# Adafruit_Feather_ESP32-C6-AUSSEN.net
KiCad netlist of a schematic drawn in EAGLE
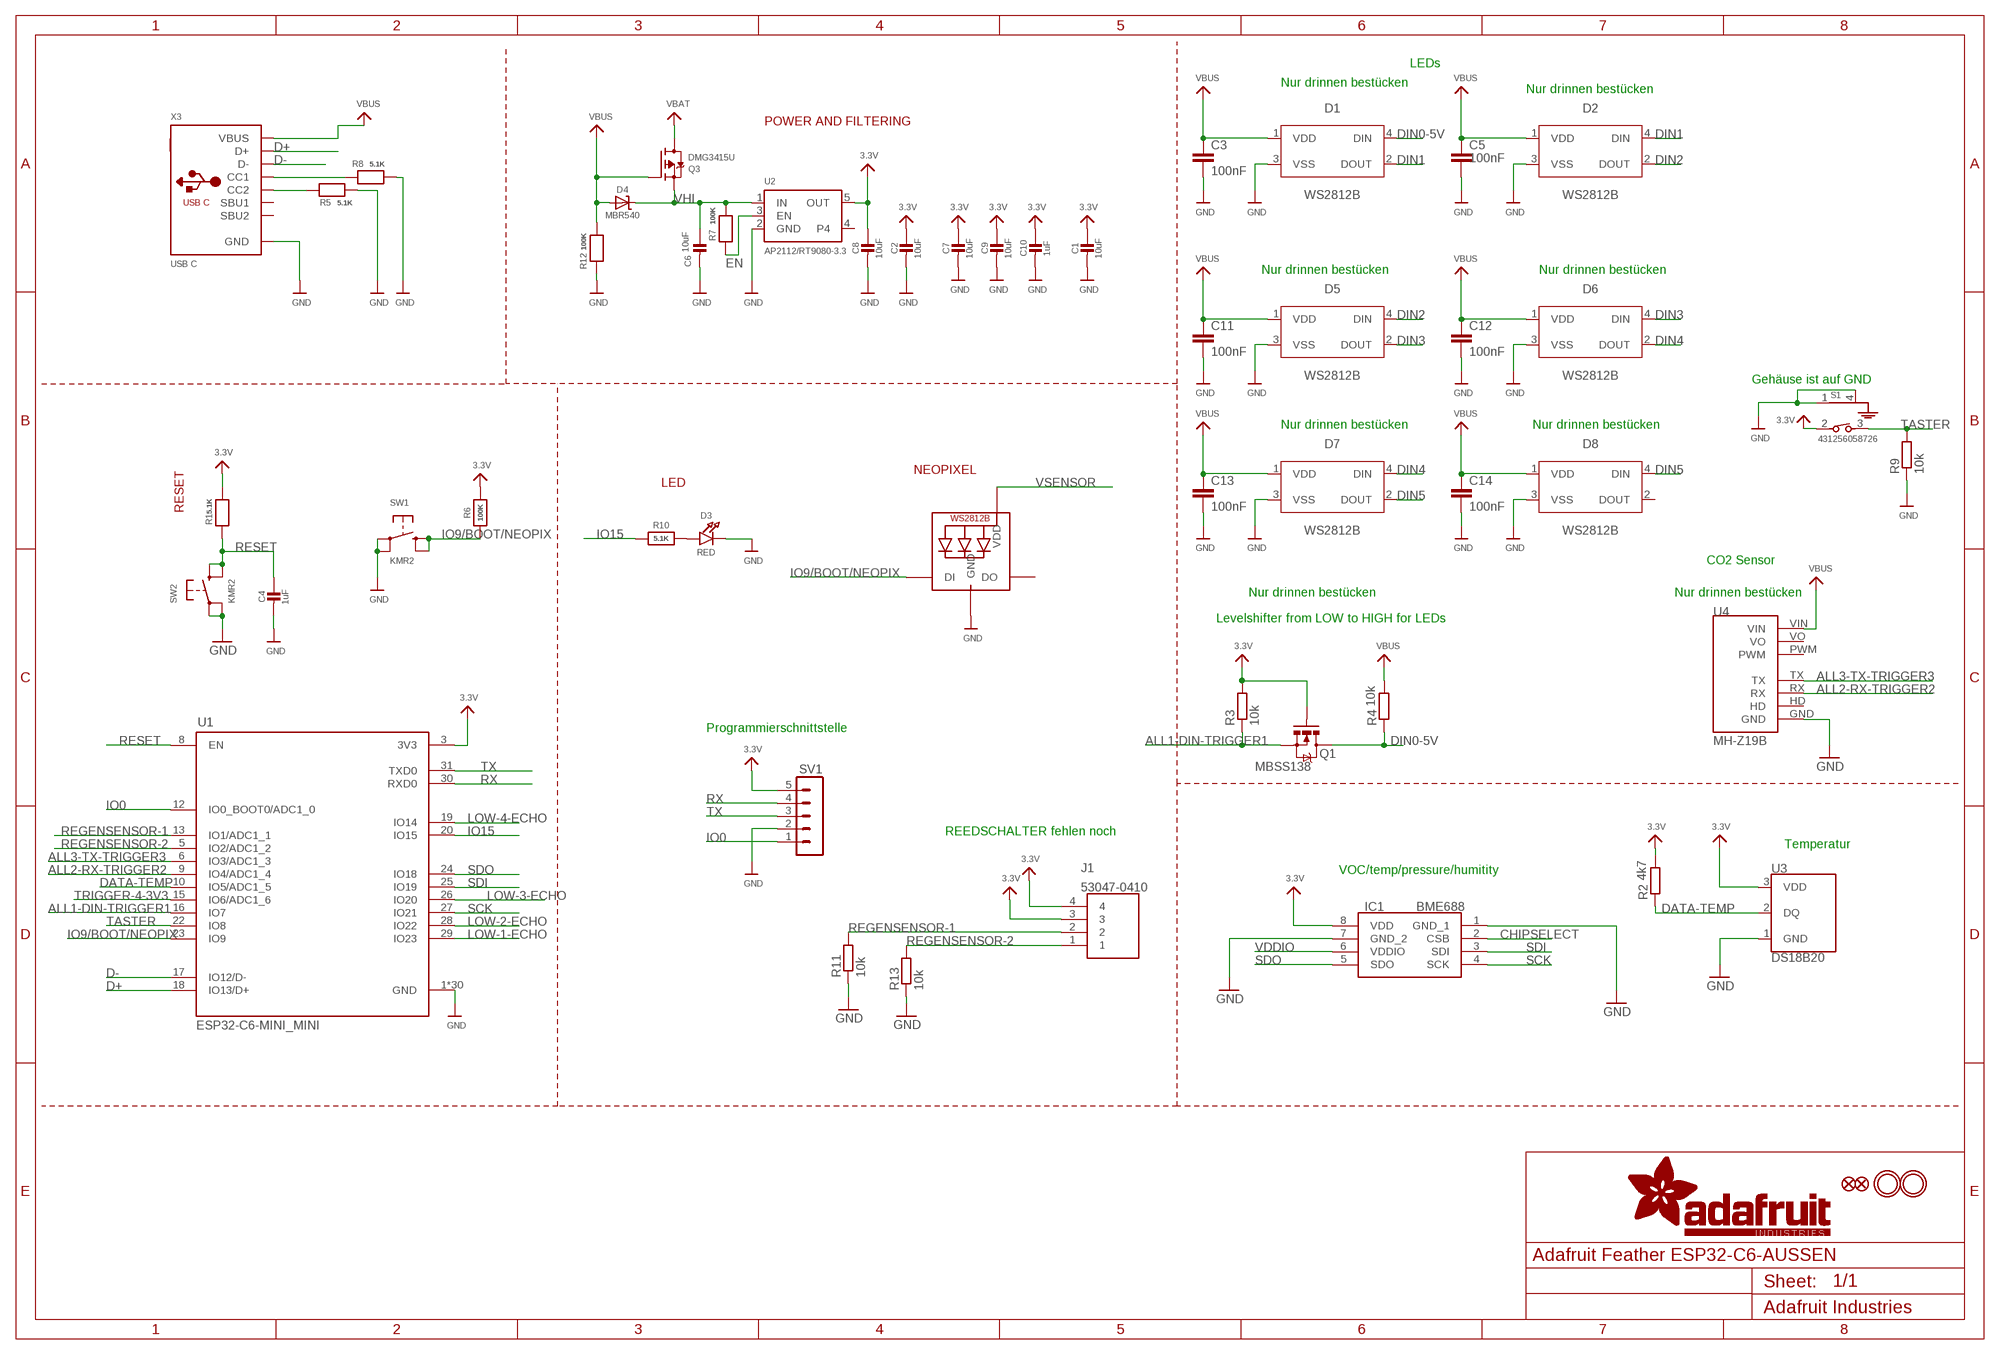
[diagram p0: schematic, sheet 1, part 1 of 2]
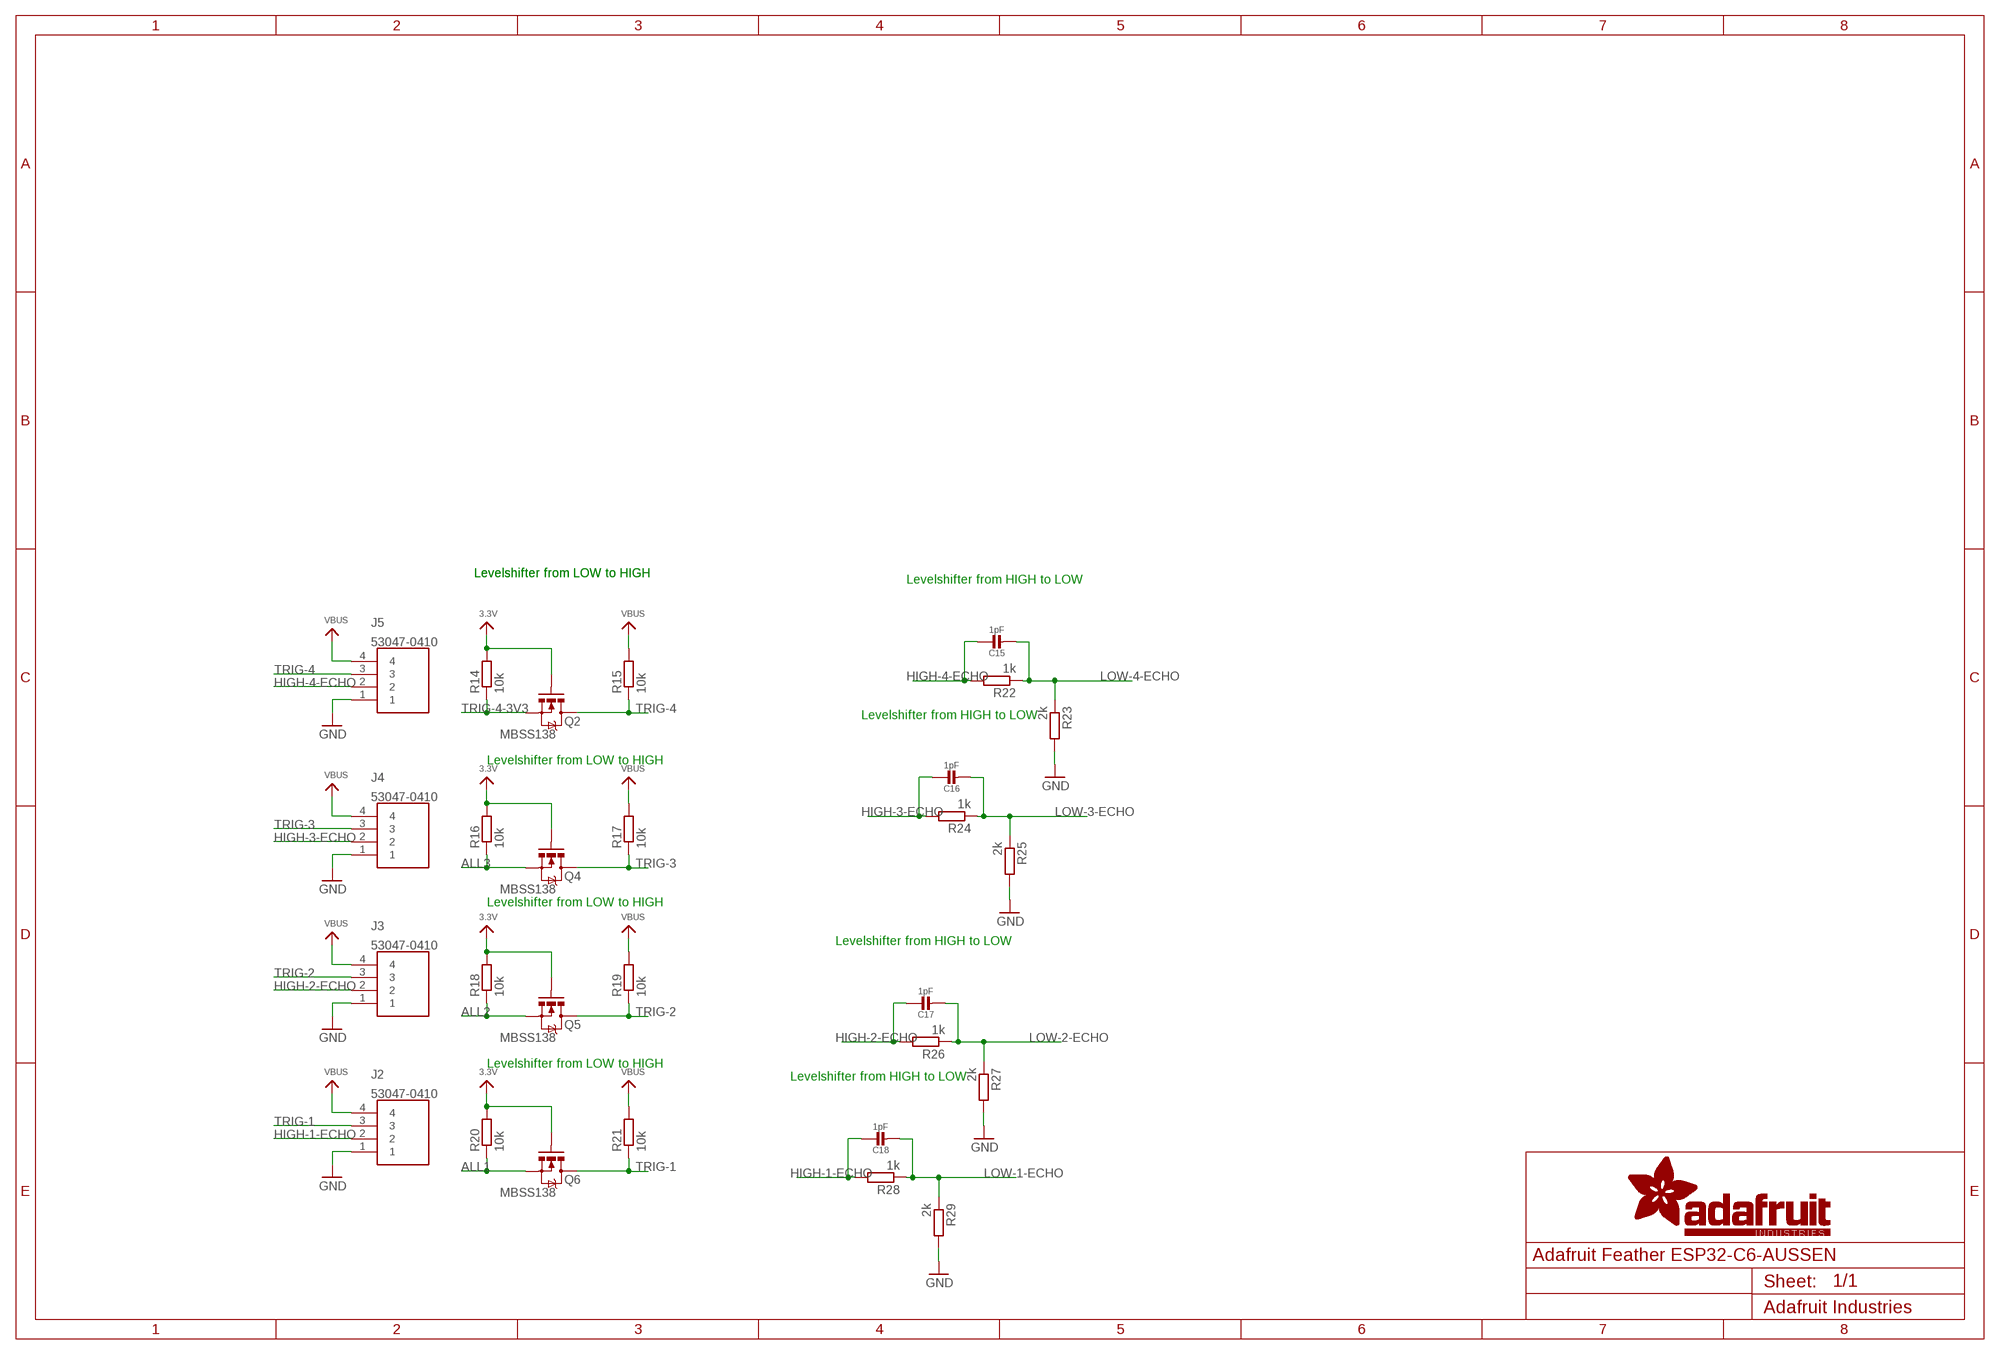
[diagram p1: schematic, sheet 1, part 2 of 2]

(export (version "E")
  (design (tool "Eeschema 10.0.6"))
  (components
    (comp (ref "C1")
      (value "10uF")
      (footprint "eagle-import:0805-NO")
      (libsource (lib "eagle-import") (part "CAP_CERAMIC0805-NOOUTLINE"))
    )
    (comp (ref "C2")
      (value "10uF")
      (footprint "eagle-import:0805-NO")
      (libsource (lib "eagle-import") (part "CAP_CERAMIC0805-NOOUTLINE"))
    )
    (comp (ref "C3")
      (value "100nF")
      (footprint "eagle-import:C0603")
      (libsource (lib "eagle-import") (part "C-EUC0603"))
    )
    (comp (ref "C4")
      (value "1uF")
      (footprint "eagle-import:0603-NO")
      (libsource (lib "eagle-import") (part "CAP_CERAMIC0603_NO"))
    )
    (comp (ref "C5")
      (value "100nF")
      (footprint "eagle-import:C0603")
      (libsource (lib "eagle-import") (part "C-EUC0603"))
    )
    (comp (ref "C6")
      (value "10uF")
      (footprint "eagle-import:0805-NO")
      (libsource (lib "eagle-import") (part "CAP_CERAMIC0805-NOOUTLINE"))
    )
    (comp (ref "C7")
      (value "10uF")
      (footprint "eagle-import:0805-NO")
      (libsource (lib "eagle-import") (part "CAP_CERAMIC0805-NOOUTLINE"))
    )
    (comp (ref "C8")
      (value "10uF")
      (footprint "eagle-import:0805-NO")
      (fields (field (name "REV") "B"))
      (libsource (lib "eagle-import") (part "CAP_CERAMIC0805-NOOUTLINE"))
    )
    (comp (ref "C9")
      (value "10uF")
      (footprint "eagle-import:0805-NO")
      (libsource (lib "eagle-import") (part "CAP_CERAMIC0805-NOOUTLINE"))
    )
    (comp (ref "C10")
      (value "1uF")
      (footprint "eagle-import:0603-NO")
      (libsource (lib "eagle-import") (part "CAP_CERAMIC0603_NO"))
    )
    (comp (ref "C11")
      (value "100nF")
      (footprint "eagle-import:C0603")
      (libsource (lib "eagle-import") (part "C-EUC0603"))
    )
    (comp (ref "C12")
      (value "100nF")
      (footprint "eagle-import:C0603")
      (libsource (lib "eagle-import") (part "C-EUC0603"))
    )
    (comp (ref "C13")
      (value "100nF")
      (footprint "eagle-import:C0603")
      (libsource (lib "eagle-import") (part "C-EUC0603"))
    )
    (comp (ref "C14")
      (value "100nF")
      (footprint "eagle-import:C0603")
      (libsource (lib "eagle-import") (part "C-EUC0603"))
    )
    (comp (ref "C15")
      (value "1pF")
      (footprint "eagle-import:0603-NO")
      (libsource (lib "eagle-import") (part "CAP_CERAMIC0603_NO"))
    )
    (comp (ref "C16")
      (value "1pF")
      (footprint "eagle-import:0603-NO")
      (libsource (lib "eagle-import") (part "CAP_CERAMIC0603_NO"))
    )
    (comp (ref "C17")
      (value "1pF")
      (footprint "eagle-import:0603-NO")
      (libsource (lib "eagle-import") (part "CAP_CERAMIC0603_NO"))
    )
    (comp (ref "C18")
      (value "1pF")
      (footprint "eagle-import:0603-NO")
      (libsource (lib "eagle-import") (part "CAP_CERAMIC0603_NO"))
    )
    (comp (ref "D1")
      (value "WS2812B")
      (footprint "eagle-import:WS2812B")
      (fields (field (name "MANUFACTURER") "Worldsemi"))
      (libsource (lib "eagle-import") (part "WS2812B"))
    )
    (comp (ref "D2")
      (value "WS2812B")
      (footprint "eagle-import:WS2812B")
      (fields (field (name "MANUFACTURER") "Worldsemi"))
      (libsource (lib "eagle-import") (part "WS2812B"))
    )
    (comp (ref "D3")
      (value "RED")
      (footprint "eagle-import:CHIPLED_0603_NOOUTLINE")
      (libsource (lib "eagle-import") (part "LED0603_NOOUTLINE"))
    )
    (comp (ref "D4")
      (value "MBR540")
      (footprint "eagle-import:SOD-123")
      (libsource (lib "eagle-import") (part "DIODE-SCHOTTKYSOD-123"))
    )
    (comp (ref "D5")
      (value "WS2812B")
      (footprint "eagle-import:WS2812B")
      (fields (field (name "MANUFACTURER") "Worldsemi"))
      (libsource (lib "eagle-import") (part "WS2812B"))
    )
    (comp (ref "D6")
      (value "WS2812B")
      (footprint "eagle-import:WS2812B")
      (fields (field (name "MANUFACTURER") "Worldsemi"))
      (libsource (lib "eagle-import") (part "WS2812B"))
    )
    (comp (ref "D7")
      (value "WS2812B")
      (footprint "eagle-import:WS2812B")
      (fields (field (name "MANUFACTURER") "Worldsemi"))
      (libsource (lib "eagle-import") (part "WS2812B"))
    )
    (comp (ref "D8")
      (value "WS2812B")
      (footprint "eagle-import:WS2812B")
      (fields (field (name "MANUFACTURER") "Worldsemi"))
      (libsource (lib "eagle-import") (part "WS2812B"))
    )
    (comp (ref "IC1")
      (value "BME688")
      (footprint "eagle-import:BME688")
      (fields (field (name "MOUSER_PART_NUMBER") "262-BME688"))
      (libsource (lib "eagle-import") (part "BME688"))
    )
    (comp (ref "J1")
      (value "53047-0410")
      (footprint "eagle-import:530470410")
      (fields (field (name "MOUSER_PART_NUMBER") "538-53047-0410"))
      (libsource (lib "eagle-import") (part "53047-0410"))
    )
    (comp (ref "J2")
      (value "53047-0410")
      (footprint "eagle-import:530470410")
      (fields (field (name "MOUSER_PART_NUMBER") "538-53047-0410"))
      (libsource (lib "eagle-import") (part "53047-0410"))
    )
    (comp (ref "J3")
      (value "53047-0410")
      (footprint "eagle-import:530470410")
      (fields (field (name "MOUSER_PART_NUMBER") "538-53047-0410"))
      (libsource (lib "eagle-import") (part "53047-0410"))
    )
    (comp (ref "J4")
      (value "53047-0410")
      (footprint "eagle-import:530470410")
      (fields (field (name "MOUSER_PART_NUMBER") "538-53047-0410"))
      (libsource (lib "eagle-import") (part "53047-0410"))
    )
    (comp (ref "J5")
      (value "53047-0410")
      (footprint "eagle-import:530470410")
      (fields (field (name "MOUSER_PART_NUMBER") "538-53047-0410"))
      (libsource (lib "eagle-import") (part "53047-0410"))
    )
    (comp (ref "LED1")
      (value "WS2812B_3535FULL")
      (footprint "eagle-import:LED3535_FULLPADS")
      (libsource (lib "eagle-import") (part "WS2812B_3535FULL"))
    )
    (comp (ref "Q1")
      (value "MBSS138")
      (footprint "eagle-import:SOT23")
      (libsource (lib "eagle-import") (part "MOSFET-NCHANNELBSS138"))
    )
    (comp (ref "Q2")
      (value "MBSS138")
      (footprint "eagle-import:SOT23")
      (libsource (lib "eagle-import") (part "MOSFET-NCHANNELBSS138"))
    )
    (comp (ref "Q3")
      (value "DMG3415U")
      (footprint "eagle-import:SOT23-R")
      (libsource (lib "eagle-import") (part "MOSFET-P"))
    )
    (comp (ref "Q4")
      (value "MBSS138")
      (footprint "eagle-import:SOT23")
      (libsource (lib "eagle-import") (part "MOSFET-NCHANNELBSS138"))
    )
    (comp (ref "Q5")
      (value "MBSS138")
      (footprint "eagle-import:SOT23")
      (libsource (lib "eagle-import") (part "MOSFET-NCHANNELBSS138"))
    )
    (comp (ref "Q6")
      (value "MBSS138")
      (footprint "eagle-import:SOT23")
      (libsource (lib "eagle-import") (part "MOSFET-NCHANNELBSS138"))
    )
    (comp (ref "R1")
      (value "5.1K")
      (footprint "eagle-import:0603-NO")
      (libsource (lib "eagle-import") (part "RESISTOR_0603_NOOUT"))
    )
    (comp (ref "R2")
      (value "4k7")
      (footprint "eagle-import:0207_12")
      (libsource (lib "eagle-import") (part "R-EU_0207/12"))
    )
    (comp (ref "R3")
      (value "10k")
      (footprint "eagle-import:0207_12")
      (libsource (lib "eagle-import") (part "R-EU_0207/12"))
    )
    (comp (ref "R4")
      (value "10k")
      (footprint "eagle-import:0207_12")
      (libsource (lib "eagle-import") (part "R-EU_0207/12"))
    )
    (comp (ref "R5")
      (value "5.1K")
      (footprint "eagle-import:0603-NO")
      (libsource (lib "eagle-import") (part "RESISTOR_0603_NOOUT"))
    )
    (comp (ref "R6")
      (value "100K")
      (footprint "eagle-import:0603-NO")
      (libsource (lib "eagle-import") (part "RESISTOR_0603_NOOUT"))
    )
    (comp (ref "R7")
      (value "100K")
      (footprint "eagle-import:0603-NO")
      (libsource (lib "eagle-import") (part "RESISTOR_0603_NOOUT"))
    )
    (comp (ref "R8")
      (value "5.1K")
      (footprint "eagle-import:0603-NO")
      (libsource (lib "eagle-import") (part "RESISTOR_0603_NOOUT"))
    )
    (comp (ref "R9")
      (value "10k")
      (footprint "eagle-import:0207_12")
      (libsource (lib "eagle-import") (part "R-EU_0207/12"))
    )
    (comp (ref "R10")
      (value "5.1K")
      (footprint "eagle-import:0603-NO")
      (libsource (lib "eagle-import") (part "RESISTOR_0603_NOOUT"))
    )
    (comp (ref "R11")
      (value "10k")
      (footprint "eagle-import:0207_12")
      (libsource (lib "eagle-import") (part "R-EU_0207/12"))
    )
    (comp (ref "R12")
      (value "100K")
      (footprint "eagle-import:0603-NO")
      (libsource (lib "eagle-import") (part "RESISTOR_0603_NOOUT"))
    )
    (comp (ref "R13")
      (value "10k")
      (footprint "eagle-import:0207_12")
      (libsource (lib "eagle-import") (part "R-EU_0207/12"))
    )
    (comp (ref "R14")
      (value "10k")
      (footprint "eagle-import:0207_12")
      (libsource (lib "eagle-import") (part "R-EU_0207/12"))
    )
    (comp (ref "R15")
      (value "10k")
      (footprint "eagle-import:0207_12")
      (libsource (lib "eagle-import") (part "R-EU_0207/12"))
    )
    (comp (ref "R16")
      (value "10k")
      (footprint "eagle-import:0207_12")
      (libsource (lib "eagle-import") (part "R-EU_0207/12"))
    )
    (comp (ref "R17")
      (value "10k")
      (footprint "eagle-import:0207_12")
      (libsource (lib "eagle-import") (part "R-EU_0207/12"))
    )
    (comp (ref "R18")
      (value "10k")
      (footprint "eagle-import:0207_12")
      (libsource (lib "eagle-import") (part "R-EU_0207/12"))
    )
    (comp (ref "R19")
      (value "10k")
      (footprint "eagle-import:0207_12")
      (libsource (lib "eagle-import") (part "R-EU_0207/12"))
    )
    (comp (ref "R20")
      (value "10k")
      (footprint "eagle-import:0207_12")
      (libsource (lib "eagle-import") (part "R-EU_0207/12"))
    )
    (comp (ref "R21")
      (value "10k")
      (footprint "eagle-import:0207_12")
      (libsource (lib "eagle-import") (part "R-EU_0207/12"))
    )
    (comp (ref "R22")
      (value "1k")
      (footprint "eagle-import:0207_12")
      (libsource (lib "eagle-import") (part "R-EU_0207/12"))
    )
    (comp (ref "R23")
      (value "2k")
      (footprint "eagle-import:0207_12")
      (libsource (lib "eagle-import") (part "R-EU_0207/12"))
    )
    (comp (ref "R24")
      (value "1k")
      (footprint "eagle-import:0207_12")
      (libsource (lib "eagle-import") (part "R-EU_0207/12"))
    )
    (comp (ref "R25")
      (value "2k")
      (footprint "eagle-import:0207_12")
      (libsource (lib "eagle-import") (part "R-EU_0207/12"))
    )
    (comp (ref "R26")
      (value "1k")
      (footprint "eagle-import:0207_12")
      (libsource (lib "eagle-import") (part "R-EU_0207/12"))
    )
    (comp (ref "R27")
      (value "2k")
      (footprint "eagle-import:0207_12")
      (libsource (lib "eagle-import") (part "R-EU_0207/12"))
    )
    (comp (ref "R28")
      (value "1k")
      (footprint "eagle-import:0207_12")
      (libsource (lib "eagle-import") (part "R-EU_0207/12"))
    )
    (comp (ref "R29")
      (value "2k")
      (footprint "eagle-import:0207_12")
      (libsource (lib "eagle-import") (part "R-EU_0207/12"))
    )
    (comp (ref "S1")
      (value "431256058726")
      (footprint "eagle-import:4312560587X6")
      (fields (field (name "MF") "Würth Elektronik") (field (name "MP") "431256058716"))
      (libsource (lib "eagle-import") (part "431256058726"))
    )
    (comp (ref "SV1")
      (value "MAR05-1")
      (footprint "eagle-import:MAR05-1")
      (libsource (lib "eagle-import") (part "MAR05-1"))
    )
    (comp (ref "SW1")
      (value "KMR2")
      (footprint "eagle-import:BTN_RKB2_4.6X2.8")
      (libsource (lib "eagle-import") (part "SWITCH_TACT_SMT_RKB2"))
    )
    (comp (ref "SW2")
      (value "KMR2")
      (footprint "eagle-import:BTN_RKB2_4.6X2.8")
      (libsource (lib "eagle-import") (part "SWITCH_TACT_SMT_RKB2"))
    )
    (comp (ref "U$31")
      (value "MOUNTINGHOLE2.5")
      (footprint "eagle-import:MOUNTINGHOLE_2.5_PLATED")
      (libsource (lib "eagle-import") (part "MOUNTINGHOLE2.5"))
    )
    (comp (ref "U$32")
      (value "MOUNTINGHOLE2.5")
      (footprint "eagle-import:MOUNTINGHOLE_2.5_PLATED")
      (libsource (lib "eagle-import") (part "MOUNTINGHOLE2.5"))
    )
    (comp (ref "U$34")
      (value "FIDUCIAL_1MM")
      (footprint "eagle-import:FIDUCIAL_1MM")
      (libsource (lib "eagle-import") (part "FIDUCIAL_1MM"))
    )
    (comp (ref "U$35")
      (value "FIDUCIAL_1MM")
      (footprint "eagle-import:FIDUCIAL_1MM")
      (libsource (lib "eagle-import") (part "FIDUCIAL_1MM"))
    )
    (comp (ref "U1")
      (value "ESP32-C6-MINI_MINI")
      (footprint "eagle-import:ESP32-PICO-MINI")
      (libsource (lib "eagle-import") (part "ESP32-C6-MINI_MINI"))
    )
    (comp (ref "U2")
      (value "AP2112/RT9080-3.3")
      (footprint "eagle-import:SOT23-5")
      (fields (field (name "JLC_ROTATION") "0"))
      (libsource (lib "eagle-import") (part "VREG_SOT23-5"))
    )
    (comp (ref "U3")
      (value "DS18B20")
      (footprint "eagle-import:TO-92-AMMO")
      (libsource (lib "eagle-import") (part "DS18B20"))
    )
    (comp (ref "U4")
      (value "MH-Z19B")
      (footprint "eagle-import:MH-Z19B")
      (fields (field (name "MF") "Winsen"))
      (libsource (lib "eagle-import") (part "MH-Z19B"))
    )
    (comp (ref "X3")
      (value "USB C")
      (footprint "eagle-import:USB_C_CUSB31-CFM2AX-01-X")
      (libsource (lib "eagle-import") (part "USB_C"))
    )
  )
  (nets
    (net (code "1") (name "/ALL1") (class "Default")
      (node (ref "Q6") (pin "2") (pinfunction "S_2") (pintype "passive"))
      (node (ref "R20") (pin "1") (pinfunction "1_1") (pintype "passive"))
    )
    (net (code "2") (name "/ALL1-DIN-TRIGGER1") (class "Default")
      (node (ref "Q1") (pin "2") (pinfunction "S_2") (pintype "passive"))
      (node (ref "R3") (pin "1") (pinfunction "1_1") (pintype "passive"))
      (node (ref "U1") (pin "16") (pinfunction "IO7_16") (pintype "bidirectional"))
    )
    (net (code "3") (name "/ALL2") (class "Default")
      (node (ref "Q5") (pin "2") (pinfunction "S_2") (pintype "passive"))
      (node (ref "R18") (pin "1") (pinfunction "1_1") (pintype "passive"))
    )
    (net (code "4") (name "/ALL2-RX-TRIGGER2") (class "Default")
      (node (ref "U1") (pin "9") (pinfunction "IO4/ADC1_4_9") (pintype "bidirectional"))
      (node (ref "U4") (pin "RX") (pinfunction "RX_RX") (pintype "bidirectional"))
    )
    (net (code "5") (name "/ALL3") (class "Default")
      (node (ref "Q4") (pin "2") (pinfunction "S_2") (pintype "passive"))
      (node (ref "R16") (pin "1") (pinfunction "1_1") (pintype "passive"))
    )
    (net (code "6") (name "/ALL3-TX-TRIGGER3") (class "Default")
      (node (ref "U1") (pin "6") (pinfunction "IO3/ADC1_3_6") (pintype "bidirectional"))
      (node (ref "U4") (pin "TX") (pinfunction "TX_TX") (pintype "bidirectional"))
    )
    (net (code "7") (name "/CHIPSELECT") (class "Default")
      (node (ref "IC1") (pin "2") (pinfunction "CSB_2") (pintype "bidirectional"))
    )
    (net (code "8") (name "/D+") (class "Default")
      (node (ref "U1") (pin "18") (pinfunction "IO13/D+_18") (pintype "bidirectional"))
      (node (ref "X3") (pin "A6") (pinfunction "D+_A6") (pintype "bidirectional"))
      (node (ref "X3") (pin "B6") (pinfunction "D+_B6") (pintype "bidirectional"))
    )
    (net (code "9") (name "/D-") (class "Default")
      (node (ref "U1") (pin "17") (pinfunction "IO12/D-_17") (pintype "bidirectional"))
      (node (ref "X3") (pin "A7") (pinfunction "D-_A7") (pintype "bidirectional"))
      (node (ref "X3") (pin "B7") (pinfunction "D-_B7") (pintype "bidirectional"))
    )
    (net (code "10") (name "/DATA-TEMP") (class "Default")
      (node (ref "R2") (pin "1") (pinfunction "1_1") (pintype "passive"))
      (node (ref "U1") (pin "10") (pinfunction "IO5/ADC1_5_10") (pintype "bidirectional"))
      (node (ref "U3") (pin "2") (pinfunction "DQ_2") (pintype "bidirectional"))
    )
    (net (code "11") (name "/DIN0-5V") (class "Default")
      (node (ref "D1") (pin "4") (pinfunction "DIN_4") (pintype "input"))
      (node (ref "Q1") (pin "3") (pinfunction "D_3") (pintype "passive"))
      (node (ref "R4") (pin "1") (pinfunction "1_1") (pintype "passive"))
    )
    (net (code "12") (name "/DIN1") (class "Default")
      (node (ref "D1") (pin "2") (pinfunction "DOUT_2") (pintype "output"))
      (node (ref "D2") (pin "4") (pinfunction "DIN_4") (pintype "input"))
    )
    (net (code "13") (name "/DIN2") (class "Default")
      (node (ref "D2") (pin "2") (pinfunction "DOUT_2") (pintype "output"))
      (node (ref "D5") (pin "4") (pinfunction "DIN_4") (pintype "input"))
    )
    (net (code "14") (name "/DIN3") (class "Default")
      (node (ref "D5") (pin "2") (pinfunction "DOUT_2") (pintype "output"))
      (node (ref "D6") (pin "4") (pinfunction "DIN_4") (pintype "input"))
    )
    (net (code "15") (name "/DIN4") (class "Default")
      (node (ref "D6") (pin "2") (pinfunction "DOUT_2") (pintype "output"))
      (node (ref "D7") (pin "4") (pinfunction "DIN_4") (pintype "input"))
    )
    (net (code "16") (name "/DIN5") (class "Default")
      (node (ref "D7") (pin "2") (pinfunction "DOUT_2") (pintype "output"))
      (node (ref "D8") (pin "4") (pinfunction "DIN_4") (pintype "input"))
    )
    (net (code "17") (name "/EN") (class "Default")
      (node (ref "R7") (pin "1") (pinfunction "1_1") (pintype "passive"))
      (node (ref "U2") (pin "3") (pinfunction "EN_3") (pintype "input"))
    )
    (net (code "18") (name "/HIGH-1-ECHO") (class "Default")
      (node (ref "C18") (pin "1") (pinfunction "1_1") (pintype "passive"))
      (node (ref "J2") (pin "2") (pinfunction "2_2") (pintype "bidirectional"))
      (node (ref "R28") (pin "2") (pinfunction "2_2") (pintype "passive"))
    )
    (net (code "19") (name "/HIGH-2-ECHO") (class "Default")
      (node (ref "C17") (pin "1") (pinfunction "1_1") (pintype "passive"))
      (node (ref "J3") (pin "2") (pinfunction "2_2") (pintype "bidirectional"))
      (node (ref "R26") (pin "2") (pinfunction "2_2") (pintype "passive"))
    )
    (net (code "20") (name "/HIGH-3-ECHO") (class "Default")
      (node (ref "C16") (pin "1") (pinfunction "1_1") (pintype "passive"))
      (node (ref "J4") (pin "2") (pinfunction "2_2") (pintype "bidirectional"))
      (node (ref "R24") (pin "2") (pinfunction "2_2") (pintype "passive"))
    )
    (net (code "21") (name "/HIGH-4-ECHO") (class "Default")
      (node (ref "C15") (pin "1") (pinfunction "1_1") (pintype "passive"))
      (node (ref "J5") (pin "2") (pinfunction "2_2") (pintype "bidirectional"))
      (node (ref "R22") (pin "2") (pinfunction "2_2") (pintype "passive"))
    )
    (net (code "22") (name "/IO0") (class "Default")
      (node (ref "SV1") (pin "1") (pinfunction "1_1") (pintype "passive"))
      (node (ref "U1") (pin "12") (pinfunction "IO0_BOOT0/ADC1_0_12") (pintype "bidirectional"))
    )
    (net (code "23") (name "/IO9{slash}BOOT{slash}NEOPIX") (class "Default")
      (node (ref "LED1") (pin "1") (pinfunction "DI_1") (pintype "input"))
      (node (ref "R6") (pin "1") (pinfunction "1_1") (pintype "passive"))
      (node (ref "SW1") (pin "B") (pinfunction "S_B") (pintype "passive"))
      (node (ref "SW1") (pin "B'") (pinfunction "S1_B'") (pintype "passive"))
      (node (ref "U1") (pin "23") (pinfunction "IO9_23") (pintype "bidirectional"))
    )
    (net (code "24") (name "/IO15") (class "Default")
      (node (ref "R10") (pin "1") (pinfunction "1_1") (pintype "passive"))
      (node (ref "U1") (pin "20") (pinfunction "IO15_20") (pintype "bidirectional"))
    )
    (net (code "25") (name "/LOW-1-ECHO") (class "Default")
      (node (ref "C18") (pin "2") (pinfunction "2_2") (pintype "passive"))
      (node (ref "R28") (pin "1") (pinfunction "1_1") (pintype "passive"))
      (node (ref "R29") (pin "1") (pinfunction "1_1") (pintype "passive"))
      (node (ref "U1") (pin "29") (pinfunction "IO23_29") (pintype "bidirectional"))
    )
    (net (code "26") (name "/LOW-2-ECHO") (class "Default")
      (node (ref "C17") (pin "2") (pinfunction "2_2") (pintype "passive"))
      (node (ref "R26") (pin "1") (pinfunction "1_1") (pintype "passive"))
      (node (ref "R27") (pin "1") (pinfunction "1_1") (pintype "passive"))
      (node (ref "U1") (pin "28") (pinfunction "IO22_28") (pintype "bidirectional"))
    )
    (net (code "27") (name "/LOW-3-ECHO") (class "Default")
      (node (ref "C16") (pin "2") (pinfunction "2_2") (pintype "passive"))
      (node (ref "R24") (pin "1") (pinfunction "1_1") (pintype "passive"))
      (node (ref "R25") (pin "1") (pinfunction "1_1") (pintype "passive"))
      (node (ref "U1") (pin "26") (pinfunction "IO20_26") (pintype "bidirectional"))
    )
    (net (code "28") (name "/LOW-4-ECHO") (class "Default")
      (node (ref "C15") (pin "2") (pinfunction "2_2") (pintype "passive"))
      (node (ref "R22") (pin "1") (pinfunction "1_1") (pintype "passive"))
      (node (ref "R23") (pin "1") (pinfunction "1_1") (pintype "passive"))
      (node (ref "U1") (pin "19") (pinfunction "IO14_19") (pintype "bidirectional"))
    )
    (net (code "29") (name "/REGENSENSOR-1") (class "Default")
      (node (ref "J1") (pin "2") (pinfunction "2_2") (pintype "bidirectional"))
      (node (ref "R11") (pin "2") (pinfunction "2_2") (pintype "passive"))
      (node (ref "U1") (pin "13") (pinfunction "IO1/ADC1_1_13") (pintype "bidirectional"))
    )
    (net (code "30") (name "/REGENSENSOR-2") (class "Default")
      (node (ref "J1") (pin "1") (pinfunction "1_1") (pintype "bidirectional"))
      (node (ref "R13") (pin "2") (pinfunction "2_2") (pintype "passive"))
      (node (ref "U1") (pin "5") (pinfunction "IO2/ADC1_2_5") (pintype "bidirectional"))
    )
    (net (code "31") (name "/RESET") (class "Default")
      (node (ref "C4") (pin "1") (pinfunction "1_1") (pintype "passive"))
      (node (ref "R1") (pin "1") (pinfunction "1_1") (pintype "passive"))
      (node (ref "SW2") (pin "B") (pinfunction "S_B") (pintype "passive"))
      (node (ref "SW2") (pin "B'") (pinfunction "S1_B'") (pintype "passive"))
      (node (ref "U1") (pin "8") (pinfunction "EN_8") (pintype "input"))
    )
    (net (code "32") (name "/RX") (class "Default")
      (node (ref "SV1") (pin "4") (pinfunction "4_4") (pintype "passive"))
      (node (ref "U1") (pin "30") (pinfunction "RXD0_30") (pintype "bidirectional"))
    )
    (net (code "33") (name "/SCK") (class "Default")
      (node (ref "IC1") (pin "4") (pinfunction "SCK_4") (pintype "bidirectional"))
      (node (ref "U1") (pin "27") (pinfunction "IO21_27") (pintype "bidirectional"))
    )
    (net (code "34") (name "/SDI") (class "Default")
      (node (ref "IC1") (pin "3") (pinfunction "SDI_3") (pintype "bidirectional"))
      (node (ref "U1") (pin "25") (pinfunction "IO19_25") (pintype "bidirectional"))
    )
    (net (code "35") (name "/SDO") (class "Default")
      (node (ref "IC1") (pin "5") (pinfunction "SDO_5") (pintype "bidirectional"))
      (node (ref "U1") (pin "24") (pinfunction "IO18_24") (pintype "bidirectional"))
    )
    (net (code "36") (name "/TASTER") (class "Default")
      (node (ref "R9") (pin "2") (pinfunction "2_2") (pintype "passive"))
      (node (ref "S1") (pin "3") (pinfunction "3_3") (pintype "passive"))
      (node (ref "U1") (pin "22") (pinfunction "IO8_22") (pintype "bidirectional"))
    )
    (net (code "37") (name "/TRIG-1") (class "Default")
      (node (ref "J2") (pin "3") (pinfunction "3_3") (pintype "bidirectional"))
      (node (ref "Q6") (pin "3") (pinfunction "D_3") (pintype "passive"))
      (node (ref "R21") (pin "1") (pinfunction "1_1") (pintype "passive"))
    )
    (net (code "38") (name "/TRIG-2") (class "Default")
      (node (ref "J3") (pin "3") (pinfunction "3_3") (pintype "bidirectional"))
      (node (ref "Q5") (pin "3") (pinfunction "D_3") (pintype "passive"))
      (node (ref "R19") (pin "1") (pinfunction "1_1") (pintype "passive"))
    )
    (net (code "39") (name "/TRIG-3") (class "Default")
      (node (ref "J4") (pin "3") (pinfunction "3_3") (pintype "bidirectional"))
      (node (ref "Q4") (pin "3") (pinfunction "D_3") (pintype "passive"))
      (node (ref "R17") (pin "1") (pinfunction "1_1") (pintype "passive"))
    )
    (net (code "40") (name "/TRIG-4") (class "Default")
      (node (ref "J5") (pin "3") (pinfunction "3_3") (pintype "bidirectional"))
      (node (ref "Q2") (pin "3") (pinfunction "D_3") (pintype "passive"))
      (node (ref "R15") (pin "1") (pinfunction "1_1") (pintype "passive"))
    )
    (net (code "41") (name "/TRIG-4-3V3") (class "Default")
      (node (ref "Q2") (pin "2") (pinfunction "S_2") (pintype "passive"))
      (node (ref "R14") (pin "1") (pinfunction "1_1") (pintype "passive"))
    )
    (net (code "42") (name "/TRIGGER-4-3V3") (class "Default")
      (node (ref "U1") (pin "15") (pinfunction "IO6/ADC1_6_15") (pintype "bidirectional"))
    )
    (net (code "43") (name "/TX") (class "Default")
      (node (ref "SV1") (pin "3") (pinfunction "3_3") (pintype "passive"))
      (node (ref "U1") (pin "31") (pinfunction "TXD0_31") (pintype "bidirectional"))
    )
    (net (code "44") (name "/VDDIO") (class "Default")
      (node (ref "IC1") (pin "6") (pinfunction "VDDIO_6") (pintype "bidirectional"))
    )
    (net (code "45") (name "/VHI") (class "Default")
      (node (ref "C6") (pin "1") (pinfunction "1_1") (pintype "passive"))
      (node (ref "D4") (pin "C") (pinfunction "C_C") (pintype "passive"))
      (node (ref "Q3") (pin "2") (pinfunction "S_2") (pintype "passive"))
      (node (ref "R7") (pin "2") (pinfunction "2_2") (pintype "passive"))
      (node (ref "U2") (pin "1") (pinfunction "IN_1") (pintype "power_in"))
    )
    (net (code "46") (name "/VSENSOR") (class "Default")
      (node (ref "LED1") (pin "2") (pinfunction "VDD_2") (pintype "power_in"))
    )
    (net (code "47") (name "3.3V") (class "Default")
      (node (ref "C1") (pin "1") (pinfunction "1_1") (pintype "passive"))
      (node (ref "C10") (pin "1") (pinfunction "1_1") (pintype "passive"))
      (node (ref "C2") (pin "1") (pinfunction "1_1") (pintype "passive"))
      (node (ref "C7") (pin "1") (pinfunction "1_1") (pintype "passive"))
      (node (ref "C8") (pin "1") (pinfunction "1_1") (pintype "passive"))
      (node (ref "C9") (pin "1") (pinfunction "1_1") (pintype "passive"))
      (node (ref "IC1") (pin "8") (pinfunction "VDD_8") (pintype "bidirectional"))
      (node (ref "J1") (pin "3") (pinfunction "3_3") (pintype "bidirectional"))
      (node (ref "J1") (pin "4") (pinfunction "4_4") (pintype "bidirectional"))
      (node (ref "Q1") (pin "1") (pinfunction "G_1") (pintype "passive"))
      (node (ref "Q2") (pin "1") (pinfunction "G_1") (pintype "passive"))
      (node (ref "Q4") (pin "1") (pinfunction "G_1") (pintype "passive"))
      (node (ref "Q5") (pin "1") (pinfunction "G_1") (pintype "passive"))
      (node (ref "Q6") (pin "1") (pinfunction "G_1") (pintype "passive"))
      (node (ref "R1") (pin "2") (pinfunction "2_2") (pintype "passive"))
      (node (ref "R14") (pin "2") (pinfunction "2_2") (pintype "passive"))
      (node (ref "R16") (pin "2") (pinfunction "2_2") (pintype "passive"))
      (node (ref "R18") (pin "2") (pinfunction "2_2") (pintype "passive"))
      (node (ref "R2") (pin "2") (pinfunction "2_2") (pintype "passive"))
      (node (ref "R20") (pin "2") (pinfunction "2_2") (pintype "passive"))
      (node (ref "R3") (pin "2") (pinfunction "2_2") (pintype "passive"))
      (node (ref "R6") (pin "2") (pinfunction "2_2") (pintype "passive"))
      (node (ref "S1") (pin "2") (pinfunction "2_2") (pintype "passive"))
      (node (ref "SV1") (pin "5") (pinfunction "5_5") (pintype "passive"))
      (node (ref "U1") (pin "3") (pinfunction "3V3_3") (pintype "power_in"))
      (node (ref "U2") (pin "5") (pinfunction "OUT_5") (pintype "power_in"))
      (node (ref "U3") (pin "3") (pinfunction "VDD_3") (pintype "power_in"))
    )
    (net (code "48") (name "GND") (class "Default")
      (node (ref "C1") (pin "2") (pinfunction "2_2") (pintype "passive"))
      (node (ref "C10") (pin "2") (pinfunction "2_2") (pintype "passive"))
      (node (ref "C11") (pin "2") (pinfunction "2_2") (pintype "passive"))
      (node (ref "C12") (pin "2") (pinfunction "2_2") (pintype "passive"))
      (node (ref "C13") (pin "2") (pinfunction "2_2") (pintype "passive"))
      (node (ref "C14") (pin "2") (pinfunction "2_2") (pintype "passive"))
      (node (ref "C2") (pin "2") (pinfunction "2_2") (pintype "passive"))
      (node (ref "C3") (pin "2") (pinfunction "2_2") (pintype "passive"))
      (node (ref "C4") (pin "2") (pinfunction "2_2") (pintype "passive"))
      (node (ref "C5") (pin "2") (pinfunction "2_2") (pintype "passive"))
      (node (ref "C6") (pin "2") (pinfunction "2_2") (pintype "passive"))
      (node (ref "C7") (pin "2") (pinfunction "2_2") (pintype "passive"))
      (node (ref "C8") (pin "2") (pinfunction "2_2") (pintype "passive"))
      (node (ref "C9") (pin "2") (pinfunction "2_2") (pintype "passive"))
      (node (ref "D1") (pin "3") (pinfunction "VSS_3") (pintype "power_in"))
      (node (ref "D2") (pin "3") (pinfunction "VSS_3") (pintype "power_in"))
      (node (ref "D3") (pin "C") (pinfunction "C_C") (pintype "passive"))
      (node (ref "D5") (pin "3") (pinfunction "VSS_3") (pintype "power_in"))
      (node (ref "D6") (pin "3") (pinfunction "VSS_3") (pintype "power_in"))
      (node (ref "D7") (pin "3") (pinfunction "VSS_3") (pintype "power_in"))
      (node (ref "D8") (pin "3") (pinfunction "VSS_3") (pintype "power_in"))
      (node (ref "IC1") (pin "1") (pinfunction "GND_1_1") (pintype "bidirectional"))
      (node (ref "IC1") (pin "7") (pinfunction "GND_2_7") (pintype "bidirectional"))
      (node (ref "J2") (pin "1") (pinfunction "1_1") (pintype "bidirectional"))
      (node (ref "J3") (pin "1") (pinfunction "1_1") (pintype "bidirectional"))
      (node (ref "J4") (pin "1") (pinfunction "1_1") (pintype "bidirectional"))
      (node (ref "J5") (pin "1") (pinfunction "1_1") (pintype "bidirectional"))
      (node (ref "LED1") (pin "4") (pinfunction "GND_4") (pintype "power_in"))
      (node (ref "R11") (pin "1") (pinfunction "1_1") (pintype "passive"))
      (node (ref "R12") (pin "1") (pinfunction "1_1") (pintype "passive"))
      (node (ref "R13") (pin "1") (pinfunction "1_1") (pintype "passive"))
      (node (ref "R23") (pin "2") (pinfunction "2_2") (pintype "passive"))
      (node (ref "R25") (pin "2") (pinfunction "2_2") (pintype "passive"))
      (node (ref "R27") (pin "2") (pinfunction "2_2") (pintype "passive"))
      (node (ref "R29") (pin "2") (pinfunction "2_2") (pintype "passive"))
      (node (ref "R5") (pin "1") (pinfunction "1_1") (pintype "passive"))
      (node (ref "R8") (pin "1") (pinfunction "1_1") (pintype "passive"))
      (node (ref "R9") (pin "1") (pinfunction "1_1") (pintype "passive"))
      (node (ref "S1") (pin "1") (pinfunction "GND1_1") (pintype "passive"))
      (node (ref "S1") (pin "4") (pinfunction "GND_4") (pintype "passive"))
      (node (ref "SV1") (pin "2") (pinfunction "2_2") (pintype "passive"))
      (node (ref "SW1") (pin "A") (pinfunction "P_A") (pintype "passive"))
      (node (ref "SW1") (pin "A'") (pinfunction "P1_A'") (pintype "passive"))
      (node (ref "SW2") (pin "A") (pinfunction "P_A") (pintype "passive"))
      (node (ref "SW2") (pin "A'") (pinfunction "P1_A'") (pintype "passive"))
      (node (ref "U1") (pin "1") (pinfunction "GND_1") (pintype "power_in"))
      (node (ref "U1") (pin "11") (pinfunction "GND_11") (pintype "power_in"))
      (node (ref "U1") (pin "14") (pinfunction "GND_14") (pintype "power_in"))
      (node (ref "U1") (pin "2") (pinfunction "GND_2") (pintype "power_in"))
      (node (ref "U1") (pin "36") (pinfunction "GND_36") (pintype "power_in"))
      (node (ref "U1") (pin "37") (pinfunction "GND_37") (pintype "power_in"))
      (node (ref "U1") (pin "38") (pinfunction "GND_38") (pintype "power_in"))
      (node (ref "U1") (pin "39") (pinfunction "GND_39") (pintype "power_in"))
      (node (ref "U1") (pin "40") (pinfunction "GND_40") (pintype "power_in"))
      (node (ref "U1") (pin "41") (pinfunction "GND_41") (pintype "power_in"))
      (node (ref "U1") (pin "42") (pinfunction "GND_42") (pintype "power_in"))
      (node (ref "U1") (pin "43") (pinfunction "GND_43") (pintype "power_in"))
      (node (ref "U1") (pin "44") (pinfunction "GND_44") (pintype "power_in"))
      (node (ref "U1") (pin "45") (pinfunction "GND_45") (pintype "power_in"))
      (node (ref "U1") (pin "46") (pinfunction "GND_46") (pintype "power_in"))
      (node (ref "U1") (pin "47") (pinfunction "GND_47") (pintype "power_in"))
      (node (ref "U1") (pin "48") (pinfunction "GND_48") (pintype "power_in"))
      (node (ref "U1") (pin "49") (pinfunction "GND_49") (pintype "power_in"))
      (node (ref "U1") (pin "50") (pinfunction "GND_50") (pintype "power_in"))
      (node (ref "U1") (pin "51") (pinfunction "GND_51") (pintype "power_in"))
      (node (ref "U1") (pin "52") (pinfunction "GND_52") (pintype "power_in"))
      (node (ref "U1") (pin "53") (pinfunction "GND_53") (pintype "power_in"))
      (node (ref "U1") (pin "54") (pinfunction "GND_54") (pintype "power_in"))
      (node (ref "U1") (pin "55") (pinfunction "GND_55") (pintype "power_in"))
      (node (ref "U1") (pin "56") (pinfunction "GND_56") (pintype "power_in"))
      (node (ref "U1") (pin "57") (pinfunction "GND_57") (pintype "power_in"))
      (node (ref "U1") (pin "58") (pinfunction "GND_58") (pintype "power_in"))
      (node (ref "U1") (pin "59") (pinfunction "GND_59") (pintype "power_in"))
      (node (ref "U1") (pin "60") (pinfunction "GND_60") (pintype "power_in"))
      (node (ref "U1") (pin "61") (pinfunction "GND_61") (pintype "power_in"))
      (node (ref "U2") (pin "2") (pinfunction "GND_2") (pintype "power_in"))
      (node (ref "U3") (pin "1") (pinfunction "GND_1") (pintype "power_in"))
      (node (ref "U4") (pin "GND") (pinfunction "GND_GND") (pintype "bidirectional"))
      (node (ref "X3") (pin "A1B12") (pinfunction "GND_A1B12") (pintype "power_in"))
      (node (ref "X3") (pin "B1A12") (pinfunction "GND_B1A12") (pintype "power_in"))
    )
    (net (code "49") (name "Net-(D3-PadA)") (class "Default")
      (node (ref "D3") (pin "A") (pinfunction "A_A") (pintype "passive"))
      (node (ref "R10") (pin "2") (pinfunction "2_2") (pintype "passive"))
    )
    (net (code "50") (name "Net-(X3-CC1)") (class "Default")
      (node (ref "R8") (pin "2") (pinfunction "2_2") (pintype "passive"))
      (node (ref "X3") (pin "A5") (pinfunction "CC1_A5") (pintype "bidirectional"))
    )
    (net (code "51") (name "Net-(X3-CC2)") (class "Default")
      (node (ref "R5") (pin "2") (pinfunction "2_2") (pintype "passive"))
      (node (ref "X3") (pin "B5") (pinfunction "CC2_B5") (pintype "bidirectional"))
    )
    (net (code "52") (name "VBAT") (class "Default")
      (node (ref "Q3") (pin "3") (pinfunction "D_3") (pintype "passive"))
    )
    (net (code "53") (name "VBUS") (class "Default")
      (node (ref "C11") (pin "1") (pinfunction "1_1") (pintype "passive"))
      (node (ref "C12") (pin "1") (pinfunction "1_1") (pintype "passive"))
      (node (ref "C13") (pin "1") (pinfunction "1_1") (pintype "passive"))
      (node (ref "C14") (pin "1") (pinfunction "1_1") (pintype "passive"))
      (node (ref "C3") (pin "1") (pinfunction "1_1") (pintype "passive"))
      (node (ref "C5") (pin "1") (pinfunction "1_1") (pintype "passive"))
      (node (ref "D1") (pin "1") (pinfunction "VDD_1") (pintype "power_in"))
      (node (ref "D2") (pin "1") (pinfunction "VDD_1") (pintype "power_in"))
      (node (ref "D4") (pin "A") (pinfunction "A_A") (pintype "passive"))
      (node (ref "D5") (pin "1") (pinfunction "VDD_1") (pintype "power_in"))
      (node (ref "D6") (pin "1") (pinfunction "VDD_1") (pintype "power_in"))
      (node (ref "D7") (pin "1") (pinfunction "VDD_1") (pintype "power_in"))
      (node (ref "D8") (pin "1") (pinfunction "VDD_1") (pintype "power_in"))
      (node (ref "J2") (pin "4") (pinfunction "4_4") (pintype "bidirectional"))
      (node (ref "J3") (pin "4") (pinfunction "4_4") (pintype "bidirectional"))
      (node (ref "J4") (pin "4") (pinfunction "4_4") (pintype "bidirectional"))
      (node (ref "J5") (pin "4") (pinfunction "4_4") (pintype "bidirectional"))
      (node (ref "Q3") (pin "1") (pinfunction "G_1") (pintype "passive"))
      (node (ref "R12") (pin "2") (pinfunction "2_2") (pintype "passive"))
      (node (ref "R15") (pin "2") (pinfunction "2_2") (pintype "passive"))
      (node (ref "R17") (pin "2") (pinfunction "2_2") (pintype "passive"))
      (node (ref "R19") (pin "2") (pinfunction "2_2") (pintype "passive"))
      (node (ref "R21") (pin "2") (pinfunction "2_2") (pintype "passive"))
      (node (ref "R4") (pin "2") (pinfunction "2_2") (pintype "passive"))
      (node (ref "U4") (pin "VIN") (pinfunction "VIN_VIN") (pintype "bidirectional"))
      (node (ref "X3") (pin "A4B9") (pinfunction "VBUS_A4B9") (pintype "power_in"))
      (node (ref "X3") (pin "B4A9") (pinfunction "VBUS_B4A9") (pintype "power_in"))
    )
    (net (code "54") (name "unconnected-(D8-DOUT-Pad2)") (class "Default")
      (node (ref "D8") (pin "2") (pinfunction "DOUT_2") (pintype "output"))
    )
    (net (code "55") (name "unconnected-(LED1-DO-Pad3)") (class "Default")
      (node (ref "LED1") (pin "3") (pinfunction "DO_3") (pintype "output"))
    )
    (net (code "56") (name "unconnected-(U2-P4-Pad4)") (class "Default")
      (node (ref "U2") (pin "4") (pinfunction "P4_4") (pintype "bidirectional"))
    )
    (net (code "57") (name "unconnected-(U4-PadHD)") (class "Default")
      (node (ref "U4") (pin "HD") (pinfunction "HD_HD") (pintype "bidirectional"))
    )
    (net (code "58") (name "unconnected-(U4-PadPWM)") (class "Default")
      (node (ref "U4") (pin "PWM") (pinfunction "PWM_PWM") (pintype "bidirectional"))
    )
    (net (code "59") (name "unconnected-(U4-PadVO)") (class "Default")
      (node (ref "U4") (pin "VO") (pinfunction "VO_VO") (pintype "bidirectional"))
    )
    (net (code "60") (name "unconnected-(X3-SBU1-PadA8)") (class "Default")
      (node (ref "X3") (pin "A8") (pinfunction "SBU1_A8") (pintype "bidirectional"))
    )
    (net (code "61") (name "unconnected-(X3-SBU2-PadB8)") (class "Default")
      (node (ref "X3") (pin "B8") (pinfunction "SBU2_B8") (pintype "bidirectional"))
    )
  )
)
